# Sumo_control.net
KiCad netlist of a schematic drawn in EAGLE
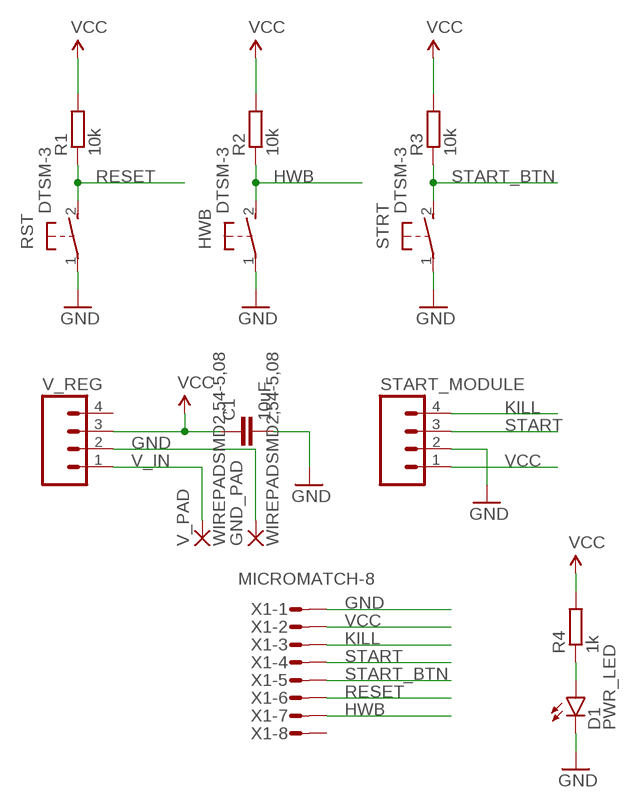
[diagram p0: schematic, sheet 1]

(export (version "E")
  (design (tool "Eeschema 10.0.6"))
  (components
    (comp (ref "C1")
      (value "10uF")
      (footprint "eagle-import:0603-CAP")
      (libsource (lib "eagle-import") (part "CAP0603-CAP"))
    )
    (comp (ref "D1")
      (value "PWR_LED")
      (footprint "eagle-import:LED-0603")
      (libsource (lib "eagle-import") (part "LED0603"))
    )
    (comp (ref "GND_PAD")
      (value "WIREPADSMD2,54-5,08")
      (footprint "eagle-import:SMD2,54-5,08")
      (libsource (lib "eagle-import") (part "WIREPADSMD2,54-5,08"))
    )
    (comp (ref "HWB")
      (value "DTSM-3")
      (footprint "eagle-import:DTSM-3")
      (libsource (lib "eagle-import") (part "DTSM-3"))
    )
    (comp (ref "R1")
      (value "10k")
      (footprint "eagle-import:R0603")
      (libsource (lib "eagle-import") (part "R-EU_R0603"))
    )
    (comp (ref "R2")
      (value "10k")
      (footprint "eagle-import:R0603")
      (libsource (lib "eagle-import") (part "R-EU_R0603"))
    )
    (comp (ref "R3")
      (value "10k")
      (footprint "eagle-import:R0603")
      (libsource (lib "eagle-import") (part "R-EU_R0603"))
    )
    (comp (ref "R4")
      (value "1k")
      (footprint "eagle-import:R0603")
      (libsource (lib "eagle-import") (part "R-EU_R0603"))
    )
    (comp (ref "RST")
      (value "DTSM-3")
      (footprint "eagle-import:DTSM-3")
      (libsource (lib "eagle-import") (part "DTSM-3"))
    )
    (comp (ref "START_MODULE")
      (value "M04LONGPADS")
      (footprint "eagle-import:1X04_LONGPADS")
      (libsource (lib "eagle-import") (part "M04LONGPADS"))
    )
    (comp (ref "STRT")
      (value "DTSM-3")
      (footprint "eagle-import:DTSM-3")
      (libsource (lib "eagle-import") (part "DTSM-3"))
    )
    (comp (ref "V_PAD")
      (value "WIREPADSMD2,54-5,08")
      (footprint "eagle-import:SMD2,54-5,08")
      (libsource (lib "eagle-import") (part "WIREPADSMD2,54-5,08"))
    )
    (comp (ref "V_REG")
      (value "M04LONGPADS")
      (footprint "eagle-import:1X04_LONGPADS")
      (libsource (lib "eagle-import") (part "M04LONGPADS"))
    )
    (comp (ref "X1")
      (value "MICROMATCH-8")
      (footprint "eagle-import:MICROMATCH-8")
      (fields (field (name "MF") "FARNELL") (field (name "MPN") "7-215464-8"))
      (libsource (lib "eagle-import") (part "MICROMATCH-8"))
    )
  )
  (nets
    (net (code "1") (name "/HWB") (class "Default")
      (node (ref "HWB") (pin "2") (pinfunction "2_2") (pintype "passive"))
      (node (ref "R2") (pin "1") (pinfunction "1_1") (pintype "passive"))
      (node (ref "X1") (pin "7") (pinfunction "S_7") (pintype "passive"))
    )
    (net (code "2") (name "/KILL") (class "Default")
      (node (ref "START_MODULE") (pin "4") (pinfunction "4_4") (pintype "passive"))
      (node (ref "X1") (pin "3") (pinfunction "S_3") (pintype "passive"))
    )
    (net (code "3") (name "/RESET") (class "Default")
      (node (ref "R1") (pin "1") (pinfunction "1_1") (pintype "passive"))
      (node (ref "RST") (pin "2") (pinfunction "2_2") (pintype "passive"))
      (node (ref "X1") (pin "6") (pinfunction "S_6") (pintype "passive"))
    )
    (net (code "4") (name "/START") (class "Default")
      (node (ref "START_MODULE") (pin "3") (pinfunction "3_3") (pintype "passive"))
      (node (ref "X1") (pin "4") (pinfunction "S_4") (pintype "passive"))
    )
    (net (code "5") (name "/START_BTN") (class "Default")
      (node (ref "R3") (pin "1") (pinfunction "1_1") (pintype "passive"))
      (node (ref "STRT") (pin "2") (pinfunction "2_2") (pintype "passive"))
      (node (ref "X1") (pin "5") (pinfunction "S_5") (pintype "passive"))
    )
    (net (code "6") (name "/V_IN") (class "Default")
      (node (ref "V_PAD") (pin "1") (pinfunction "P_1") (pintype "passive"))
      (node (ref "V_REG") (pin "1") (pinfunction "1_1") (pintype "passive"))
    )
    (net (code "7") (name "GND") (class "Default")
      (node (ref "C1") (pin "2") (pinfunction "2_2") (pintype "passive"))
      (node (ref "D1") (pin "C") (pinfunction "C_C") (pintype "passive"))
      (node (ref "GND_PAD") (pin "1") (pinfunction "P_1") (pintype "passive"))
      (node (ref "HWB") (pin "1") (pinfunction "1_1") (pintype "passive"))
      (node (ref "RST") (pin "1") (pinfunction "1_1") (pintype "passive"))
      (node (ref "START_MODULE") (pin "2") (pinfunction "2_2") (pintype "passive"))
      (node (ref "STRT") (pin "1") (pinfunction "1_1") (pintype "passive"))
      (node (ref "V_REG") (pin "2") (pinfunction "2_2") (pintype "passive"))
      (node (ref "X1") (pin "1") (pinfunction "S_1") (pintype "passive"))
    )
    (net (code "8") (name "Net-(D1-PadA)") (class "Default")
      (node (ref "D1") (pin "A") (pinfunction "A_A") (pintype "passive"))
      (node (ref "R4") (pin "1") (pinfunction "1_1") (pintype "passive"))
    )
    (net (code "9") (name "VCC") (class "Default")
      (node (ref "C1") (pin "1") (pinfunction "1_1") (pintype "passive"))
      (node (ref "R1") (pin "2") (pinfunction "2_2") (pintype "passive"))
      (node (ref "R2") (pin "2") (pinfunction "2_2") (pintype "passive"))
      (node (ref "R3") (pin "2") (pinfunction "2_2") (pintype "passive"))
      (node (ref "R4") (pin "2") (pinfunction "2_2") (pintype "passive"))
      (node (ref "START_MODULE") (pin "1") (pinfunction "1_1") (pintype "passive"))
      (node (ref "V_REG") (pin "3") (pinfunction "3_3") (pintype "passive"))
      (node (ref "X1") (pin "2") (pinfunction "S_2") (pintype "passive"))
    )
    (net (code "10") (name "unconnected-(V_REG-Pad4)") (class "Default")
      (node (ref "V_REG") (pin "4") (pinfunction "4_4") (pintype "passive"))
    )
    (net (code "11") (name "unconnected-(X1H-S-Pad8)") (class "Default")
      (node (ref "X1") (pin "8") (pinfunction "S_8") (pintype "passive"))
    )
  )
)
